# PCB-BI16-3x5_1.net
KiCad netlist of a schematic drawn in EAGLE
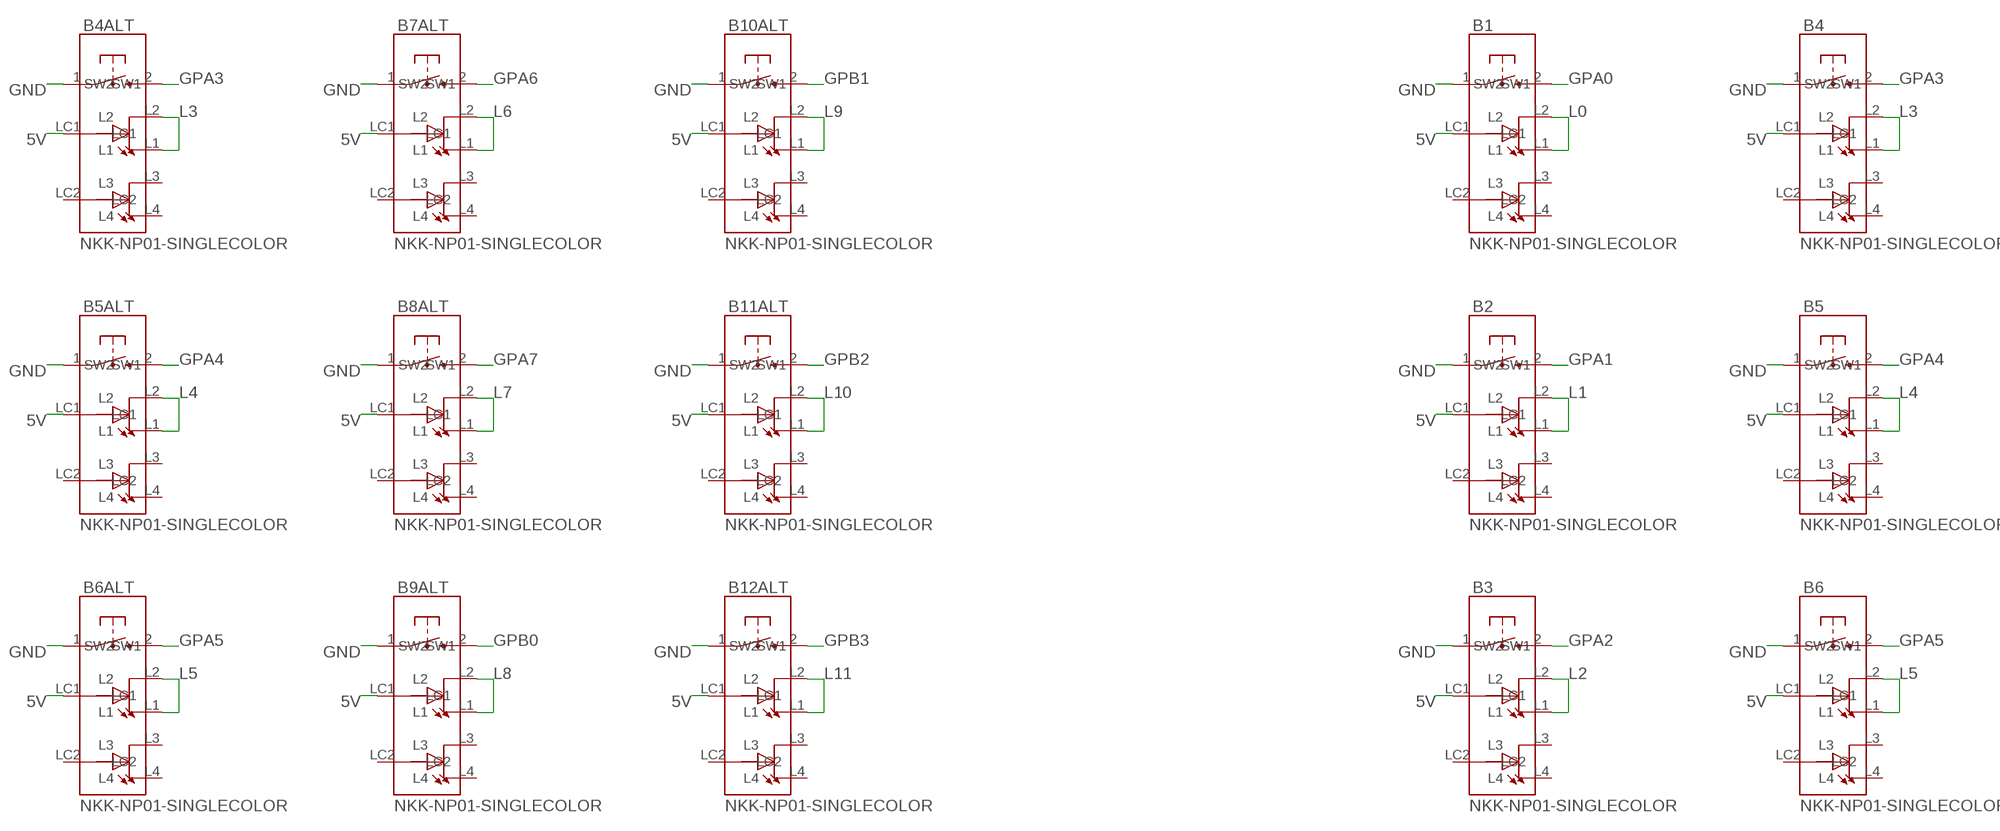
[diagram p0: schematic, sheet 1, part 1 of 2]
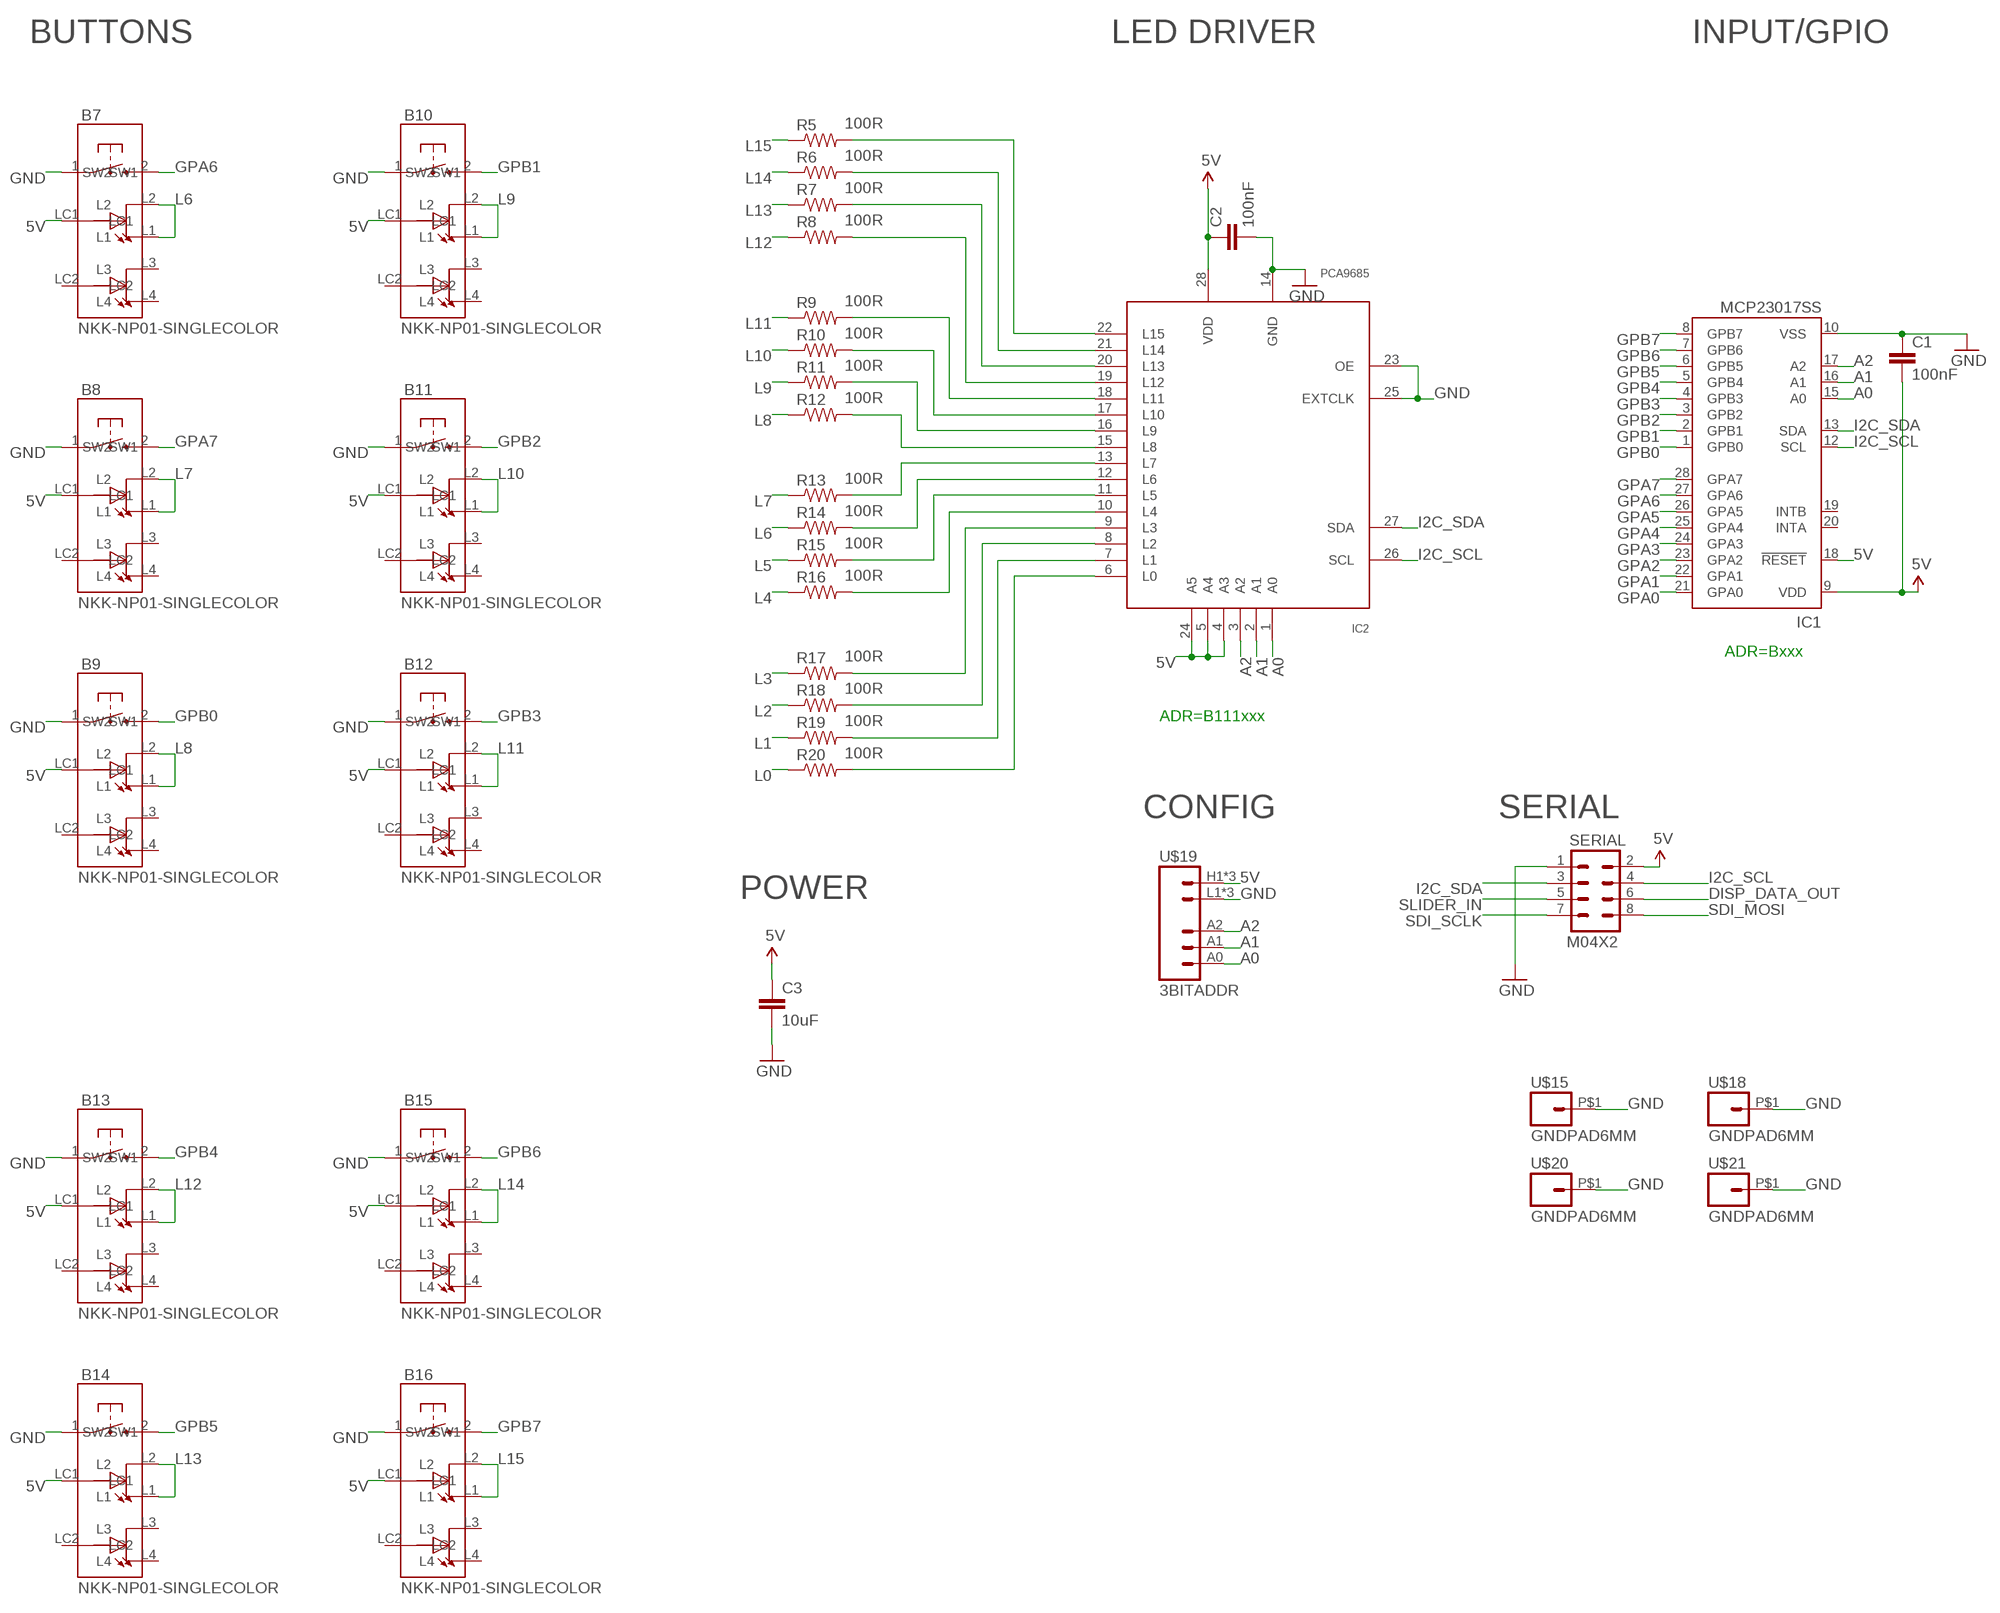
[diagram p1: schematic, sheet 1, part 2 of 2]

(export (version "E")
  (design (tool "Eeschema 10.0.6"))
  (components
    (comp (ref "B1")
      (value "NKK-NP01-SINGLECOLOR")
      (footprint "eagle-import:NKK-NP01")
      (libsource (lib "eagle-import") (part "NKK-NP01-SINGLECOLOR"))
    )
    (comp (ref "B2")
      (value "NKK-NP01-SINGLECOLOR")
      (footprint "eagle-import:NKK-NP01")
      (libsource (lib "eagle-import") (part "NKK-NP01-SINGLECOLOR"))
    )
    (comp (ref "B3")
      (value "NKK-NP01-SINGLECOLOR")
      (footprint "eagle-import:NKK-NP01")
      (libsource (lib "eagle-import") (part "NKK-NP01-SINGLECOLOR"))
    )
    (comp (ref "B4")
      (value "NKK-NP01-SINGLECOLOR")
      (footprint "eagle-import:NKK-NP01")
      (libsource (lib "eagle-import") (part "NKK-NP01-SINGLECOLOR"))
    )
    (comp (ref "B4ALT")
      (value "NKK-NP01-SINGLECOLOR")
      (footprint "eagle-import:NKK-NP01")
      (libsource (lib "eagle-import") (part "NKK-NP01-SINGLECOLOR"))
    )
    (comp (ref "B5")
      (value "NKK-NP01-SINGLECOLOR")
      (footprint "eagle-import:NKK-NP01")
      (libsource (lib "eagle-import") (part "NKK-NP01-SINGLECOLOR"))
    )
    (comp (ref "B5ALT")
      (value "NKK-NP01-SINGLECOLOR")
      (footprint "eagle-import:NKK-NP01")
      (libsource (lib "eagle-import") (part "NKK-NP01-SINGLECOLOR"))
    )
    (comp (ref "B6")
      (value "NKK-NP01-SINGLECOLOR")
      (footprint "eagle-import:NKK-NP01")
      (libsource (lib "eagle-import") (part "NKK-NP01-SINGLECOLOR"))
    )
    (comp (ref "B6ALT")
      (value "NKK-NP01-SINGLECOLOR")
      (footprint "eagle-import:NKK-NP01")
      (libsource (lib "eagle-import") (part "NKK-NP01-SINGLECOLOR"))
    )
    (comp (ref "B7")
      (value "NKK-NP01-SINGLECOLOR")
      (footprint "eagle-import:NKK-NP01")
      (libsource (lib "eagle-import") (part "NKK-NP01-SINGLECOLOR"))
    )
    (comp (ref "B7ALT")
      (value "NKK-NP01-SINGLECOLOR")
      (footprint "eagle-import:NKK-NP01")
      (libsource (lib "eagle-import") (part "NKK-NP01-SINGLECOLOR"))
    )
    (comp (ref "B8")
      (value "NKK-NP01-SINGLECOLOR")
      (footprint "eagle-import:NKK-NP01")
      (libsource (lib "eagle-import") (part "NKK-NP01-SINGLECOLOR"))
    )
    (comp (ref "B8ALT")
      (value "NKK-NP01-SINGLECOLOR")
      (footprint "eagle-import:NKK-NP01")
      (libsource (lib "eagle-import") (part "NKK-NP01-SINGLECOLOR"))
    )
    (comp (ref "B9")
      (value "NKK-NP01-SINGLECOLOR")
      (footprint "eagle-import:NKK-NP01")
      (libsource (lib "eagle-import") (part "NKK-NP01-SINGLECOLOR"))
    )
    (comp (ref "B9ALT")
      (value "NKK-NP01-SINGLECOLOR")
      (footprint "eagle-import:NKK-NP01")
      (libsource (lib "eagle-import") (part "NKK-NP01-SINGLECOLOR"))
    )
    (comp (ref "B10")
      (value "NKK-NP01-SINGLECOLOR")
      (footprint "eagle-import:NKK-NP01")
      (libsource (lib "eagle-import") (part "NKK-NP01-SINGLECOLOR"))
    )
    (comp (ref "B10ALT")
      (value "NKK-NP01-SINGLECOLOR")
      (footprint "eagle-import:NKK-NP01")
      (libsource (lib "eagle-import") (part "NKK-NP01-SINGLECOLOR"))
    )
    (comp (ref "B11")
      (value "NKK-NP01-SINGLECOLOR")
      (footprint "eagle-import:NKK-NP01")
      (libsource (lib "eagle-import") (part "NKK-NP01-SINGLECOLOR"))
    )
    (comp (ref "B11ALT")
      (value "NKK-NP01-SINGLECOLOR")
      (footprint "eagle-import:NKK-NP01")
      (libsource (lib "eagle-import") (part "NKK-NP01-SINGLECOLOR"))
    )
    (comp (ref "B12")
      (value "NKK-NP01-SINGLECOLOR")
      (footprint "eagle-import:NKK-NP01")
      (libsource (lib "eagle-import") (part "NKK-NP01-SINGLECOLOR"))
    )
    (comp (ref "B12ALT")
      (value "NKK-NP01-SINGLECOLOR")
      (footprint "eagle-import:NKK-NP01")
      (libsource (lib "eagle-import") (part "NKK-NP01-SINGLECOLOR"))
    )
    (comp (ref "B13")
      (value "NKK-NP01-SINGLECOLOR")
      (footprint "eagle-import:NKK-NP01")
      (libsource (lib "eagle-import") (part "NKK-NP01-SINGLECOLOR"))
    )
    (comp (ref "B14")
      (value "NKK-NP01-SINGLECOLOR")
      (footprint "eagle-import:NKK-NP01")
      (libsource (lib "eagle-import") (part "NKK-NP01-SINGLECOLOR"))
    )
    (comp (ref "B15")
      (value "NKK-NP01-SINGLECOLOR")
      (footprint "eagle-import:NKK-NP01")
      (libsource (lib "eagle-import") (part "NKK-NP01-SINGLECOLOR"))
    )
    (comp (ref "B16")
      (value "NKK-NP01-SINGLECOLOR")
      (footprint "eagle-import:NKK-NP01")
      (libsource (lib "eagle-import") (part "NKK-NP01-SINGLECOLOR"))
    )
    (comp (ref "C1")
      (value "100nF")
      (footprint "eagle-import:0603-CAP")
      (libsource (lib "eagle-import") (part "CAP0603-CAP"))
    )
    (comp (ref "C2")
      (value "100nF")
      (footprint "eagle-import:0603-CAP")
      (libsource (lib "eagle-import") (part "CAP0603-CAP"))
    )
    (comp (ref "C3")
      (value "10uF")
      (footprint "eagle-import:0805")
      (libsource (lib "eagle-import") (part "CAP0805"))
    )
    (comp (ref "IC1")
      (value "MCP23017SS")
      (footprint "eagle-import:SSOP28")
      (fields
        (field (name "MF") "MICROCHIP")
        (field (name "MPN") "MCP23017-E/SS")
        (field (name "MPN_1") "MCP23017-E/SS")
        (field (name "OC_FARNELL") "1467674")
        (field (name "OC_NEWARK") "31K2960")
      )
      (libsource (lib "eagle-import") (part "MCP23017SS"))
    )
    (comp (ref "IC2")
      (value "PCA9685")
      (footprint "eagle-import:TSSOP28")
      (libsource (lib "eagle-import") (part "PCA9685"))
    )
    (comp (ref "R5")
      (value "100R")
      (footprint "eagle-import:0603-RES")
      (libsource (lib "eagle-import") (part "RESISTOR0603-RES"))
    )
    (comp (ref "R6")
      (value "100R")
      (footprint "eagle-import:0603-RES")
      (libsource (lib "eagle-import") (part "RESISTOR0603-RES"))
    )
    (comp (ref "R7")
      (value "100R")
      (footprint "eagle-import:0603-RES")
      (libsource (lib "eagle-import") (part "RESISTOR0603-RES"))
    )
    (comp (ref "R8")
      (value "100R")
      (footprint "eagle-import:0603-RES")
      (libsource (lib "eagle-import") (part "RESISTOR0603-RES"))
    )
    (comp (ref "R9")
      (value "100R")
      (footprint "eagle-import:0603-RES")
      (libsource (lib "eagle-import") (part "RESISTOR0603-RES"))
    )
    (comp (ref "R10")
      (value "100R")
      (footprint "eagle-import:0603-RES")
      (libsource (lib "eagle-import") (part "RESISTOR0603-RES"))
    )
    (comp (ref "R11")
      (value "100R")
      (footprint "eagle-import:0603-RES")
      (libsource (lib "eagle-import") (part "RESISTOR0603-RES"))
    )
    (comp (ref "R12")
      (value "100R")
      (footprint "eagle-import:0603-RES")
      (libsource (lib "eagle-import") (part "RESISTOR0603-RES"))
    )
    (comp (ref "R13")
      (value "100R")
      (footprint "eagle-import:0603-RES")
      (libsource (lib "eagle-import") (part "RESISTOR0603-RES"))
    )
    (comp (ref "R14")
      (value "100R")
      (footprint "eagle-import:0603-RES")
      (libsource (lib "eagle-import") (part "RESISTOR0603-RES"))
    )
    (comp (ref "R15")
      (value "100R")
      (footprint "eagle-import:0603-RES")
      (libsource (lib "eagle-import") (part "RESISTOR0603-RES"))
    )
    (comp (ref "R16")
      (value "100R")
      (footprint "eagle-import:0603-RES")
      (libsource (lib "eagle-import") (part "RESISTOR0603-RES"))
    )
    (comp (ref "R17")
      (value "100R")
      (footprint "eagle-import:0603-RES")
      (libsource (lib "eagle-import") (part "RESISTOR0603-RES"))
    )
    (comp (ref "R18")
      (value "100R")
      (footprint "eagle-import:0603-RES")
      (libsource (lib "eagle-import") (part "RESISTOR0603-RES"))
    )
    (comp (ref "R19")
      (value "100R")
      (footprint "eagle-import:0603-RES")
      (libsource (lib "eagle-import") (part "RESISTOR0603-RES"))
    )
    (comp (ref "R20")
      (value "100R")
      (footprint "eagle-import:0603-RES")
      (libsource (lib "eagle-import") (part "RESISTOR0603-RES"))
    )
    (comp (ref "SERIAL")
      (value "M04X2")
      (footprint "eagle-import:2X4")
      (libsource (lib "eagle-import") (part "M04X2"))
    )
    (comp (ref "U$15")
      (value "GNDPAD6MM")
      (footprint "eagle-import:3.2MMPAD6MM")
      (libsource (lib "eagle-import") (part "GNDPAD6MM"))
    )
    (comp (ref "U$18")
      (value "GNDPAD6MM")
      (footprint "eagle-import:3.2MMPAD6MM")
      (libsource (lib "eagle-import") (part "GNDPAD6MM"))
    )
    (comp (ref "U$19")
      (value "3BITADDR")
      (footprint "eagle-import:3BITADDR")
      (libsource (lib "eagle-import") (part "3BITADDR"))
    )
    (comp (ref "U$20")
      (value "GNDPAD6MM")
      (footprint "eagle-import:3.2MMPAD6MM")
      (libsource (lib "eagle-import") (part "GNDPAD6MM"))
    )
    (comp (ref "U$21")
      (value "GNDPAD6MM")
      (footprint "eagle-import:3.2MMPAD6MM")
      (libsource (lib "eagle-import") (part "GNDPAD6MM"))
    )
  )
  (nets
    (net (code "1") (name "5V") (class "Default")
      (node (ref "B1") (pin "LC1") (pinfunction "LC1_LC1") (pintype "bidirectional"))
      (node (ref "B10") (pin "LC1") (pinfunction "LC1_LC1") (pintype "bidirectional"))
      (node (ref "B10ALT") (pin "LC1") (pinfunction "LC1_LC1") (pintype "bidirectional"))
      (node (ref "B11") (pin "LC1") (pinfunction "LC1_LC1") (pintype "bidirectional"))
      (node (ref "B11ALT") (pin "LC1") (pinfunction "LC1_LC1") (pintype "bidirectional"))
      (node (ref "B12") (pin "LC1") (pinfunction "LC1_LC1") (pintype "bidirectional"))
      (node (ref "B12ALT") (pin "LC1") (pinfunction "LC1_LC1") (pintype "bidirectional"))
      (node (ref "B13") (pin "LC1") (pinfunction "LC1_LC1") (pintype "bidirectional"))
      (node (ref "B14") (pin "LC1") (pinfunction "LC1_LC1") (pintype "bidirectional"))
      (node (ref "B15") (pin "LC1") (pinfunction "LC1_LC1") (pintype "bidirectional"))
      (node (ref "B16") (pin "LC1") (pinfunction "LC1_LC1") (pintype "bidirectional"))
      (node (ref "B2") (pin "LC1") (pinfunction "LC1_LC1") (pintype "bidirectional"))
      (node (ref "B3") (pin "LC1") (pinfunction "LC1_LC1") (pintype "bidirectional"))
      (node (ref "B4") (pin "LC1") (pinfunction "LC1_LC1") (pintype "bidirectional"))
      (node (ref "B4ALT") (pin "LC1") (pinfunction "LC1_LC1") (pintype "bidirectional"))
      (node (ref "B5") (pin "LC1") (pinfunction "LC1_LC1") (pintype "bidirectional"))
      (node (ref "B5ALT") (pin "LC1") (pinfunction "LC1_LC1") (pintype "bidirectional"))
      (node (ref "B6") (pin "LC1") (pinfunction "LC1_LC1") (pintype "bidirectional"))
      (node (ref "B6ALT") (pin "LC1") (pinfunction "LC1_LC1") (pintype "bidirectional"))
      (node (ref "B7") (pin "LC1") (pinfunction "LC1_LC1") (pintype "bidirectional"))
      (node (ref "B7ALT") (pin "LC1") (pinfunction "LC1_LC1") (pintype "bidirectional"))
      (node (ref "B8") (pin "LC1") (pinfunction "LC1_LC1") (pintype "bidirectional"))
      (node (ref "B8ALT") (pin "LC1") (pinfunction "LC1_LC1") (pintype "bidirectional"))
      (node (ref "B9") (pin "LC1") (pinfunction "LC1_LC1") (pintype "bidirectional"))
      (node (ref "B9ALT") (pin "LC1") (pinfunction "LC1_LC1") (pintype "bidirectional"))
      (node (ref "C1") (pin "2") (pinfunction "2_2") (pintype "passive"))
      (node (ref "C2") (pin "1") (pinfunction "1_1") (pintype "passive"))
      (node (ref "C3") (pin "1") (pinfunction "1_1") (pintype "passive"))
      (node (ref "IC1") (pin "18") (pinfunction "~{RESET}_18") (pintype "input"))
      (node (ref "IC1") (pin "9") (pinfunction "VDD_9") (pintype "power_in"))
      (node (ref "IC2") (pin "24") (pinfunction "A5_24") (pintype "input"))
      (node (ref "IC2") (pin "28") (pinfunction "VDD_28") (pintype "power_in"))
      (node (ref "IC2") (pin "4") (pinfunction "A3_4") (pintype "input"))
      (node (ref "IC2") (pin "5") (pinfunction "A4_5") (pintype "input"))
      (node (ref "SERIAL") (pin "2") (pinfunction "2_2") (pintype "passive"))
      (node (ref "U$19") (pin "H1") (pinfunction "VCC_H1") (pintype "passive"))
      (node (ref "U$19") (pin "H2") (pinfunction "VCC_H2") (pintype "passive"))
      (node (ref "U$19") (pin "H3") (pinfunction "VCC_H3") (pintype "passive"))
    )
    (net (code "2") (name "A0") (class "Default")
      (node (ref "IC1") (pin "15") (pinfunction "A0_15") (pintype "input"))
      (node (ref "IC2") (pin "1") (pinfunction "A0_1") (pintype "input"))
      (node (ref "U$19") (pin "A0") (pinfunction "A0_A0") (pintype "passive"))
    )
    (net (code "3") (name "A1") (class "Default")
      (node (ref "IC1") (pin "16") (pinfunction "A1_16") (pintype "input"))
      (node (ref "IC2") (pin "2") (pinfunction "A1_2") (pintype "input"))
      (node (ref "U$19") (pin "A1") (pinfunction "A1_A1") (pintype "passive"))
    )
    (net (code "4") (name "A2") (class "Default")
      (node (ref "IC1") (pin "17") (pinfunction "A2_17") (pintype "input"))
      (node (ref "IC2") (pin "3") (pinfunction "A2_3") (pintype "input"))
      (node (ref "U$19") (pin "A2") (pinfunction "A2_A2") (pintype "passive"))
    )
    (net (code "5") (name "DISP_DATA_OUT") (class "Default")
      (node (ref "SERIAL") (pin "6") (pinfunction "6_6") (pintype "passive"))
    )
    (net (code "6") (name "GND") (class "Default")
      (node (ref "B1") (pin "1") (pinfunction "SW1_1") (pintype "bidirectional"))
      (node (ref "B10") (pin "1") (pinfunction "SW1_1") (pintype "bidirectional"))
      (node (ref "B10ALT") (pin "1") (pinfunction "SW1_1") (pintype "bidirectional"))
      (node (ref "B11") (pin "1") (pinfunction "SW1_1") (pintype "bidirectional"))
      (node (ref "B11ALT") (pin "1") (pinfunction "SW1_1") (pintype "bidirectional"))
      (node (ref "B12") (pin "1") (pinfunction "SW1_1") (pintype "bidirectional"))
      (node (ref "B12ALT") (pin "1") (pinfunction "SW1_1") (pintype "bidirectional"))
      (node (ref "B13") (pin "1") (pinfunction "SW1_1") (pintype "bidirectional"))
      (node (ref "B14") (pin "1") (pinfunction "SW1_1") (pintype "bidirectional"))
      (node (ref "B15") (pin "1") (pinfunction "SW1_1") (pintype "bidirectional"))
      (node (ref "B16") (pin "1") (pinfunction "SW1_1") (pintype "bidirectional"))
      (node (ref "B2") (pin "1") (pinfunction "SW1_1") (pintype "bidirectional"))
      (node (ref "B3") (pin "1") (pinfunction "SW1_1") (pintype "bidirectional"))
      (node (ref "B4") (pin "1") (pinfunction "SW1_1") (pintype "bidirectional"))
      (node (ref "B4ALT") (pin "1") (pinfunction "SW1_1") (pintype "bidirectional"))
      (node (ref "B5") (pin "1") (pinfunction "SW1_1") (pintype "bidirectional"))
      (node (ref "B5ALT") (pin "1") (pinfunction "SW1_1") (pintype "bidirectional"))
      (node (ref "B6") (pin "1") (pinfunction "SW1_1") (pintype "bidirectional"))
      (node (ref "B6ALT") (pin "1") (pinfunction "SW1_1") (pintype "bidirectional"))
      (node (ref "B7") (pin "1") (pinfunction "SW1_1") (pintype "bidirectional"))
      (node (ref "B7ALT") (pin "1") (pinfunction "SW1_1") (pintype "bidirectional"))
      (node (ref "B8") (pin "1") (pinfunction "SW1_1") (pintype "bidirectional"))
      (node (ref "B8ALT") (pin "1") (pinfunction "SW1_1") (pintype "bidirectional"))
      (node (ref "B9") (pin "1") (pinfunction "SW1_1") (pintype "bidirectional"))
      (node (ref "B9ALT") (pin "1") (pinfunction "SW1_1") (pintype "bidirectional"))
      (node (ref "C1") (pin "1") (pinfunction "1_1") (pintype "passive"))
      (node (ref "C2") (pin "2") (pinfunction "2_2") (pintype "passive"))
      (node (ref "C3") (pin "2") (pinfunction "2_2") (pintype "passive"))
      (node (ref "IC1") (pin "10") (pinfunction "VSS_10") (pintype "power_in"))
      (node (ref "IC2") (pin "14") (pinfunction "GND_14") (pintype "power_in"))
      (node (ref "IC2") (pin "23") (pinfunction "OE_23") (pintype "input"))
      (node (ref "IC2") (pin "25") (pinfunction "EXTCLK_25") (pintype "input"))
      (node (ref "SERIAL") (pin "1") (pinfunction "1_1") (pintype "passive"))
      (node (ref "U$15") (pin "P$1") (pinfunction "1_P$1") (pintype "passive"))
      (node (ref "U$18") (pin "P$1") (pinfunction "1_P$1") (pintype "passive"))
      (node (ref "U$19") (pin "L1") (pinfunction "GND_L1") (pintype "passive"))
      (node (ref "U$19") (pin "L2") (pinfunction "GND_L2") (pintype "passive"))
      (node (ref "U$19") (pin "L3") (pinfunction "GND_L3") (pintype "passive"))
      (node (ref "U$20") (pin "P$1") (pinfunction "1_P$1") (pintype "passive"))
      (node (ref "U$21") (pin "P$1") (pinfunction "1_P$1") (pintype "passive"))
    )
    (net (code "7") (name "GPA0") (class "Default")
      (node (ref "B1") (pin "2") (pinfunction "SW2_2") (pintype "bidirectional"))
      (node (ref "IC1") (pin "21") (pinfunction "GPA0_21") (pintype "bidirectional"))
    )
    (net (code "8") (name "GPA1") (class "Default")
      (node (ref "B2") (pin "2") (pinfunction "SW2_2") (pintype "bidirectional"))
      (node (ref "IC1") (pin "22") (pinfunction "GPA1_22") (pintype "bidirectional"))
    )
    (net (code "9") (name "GPA2") (class "Default")
      (node (ref "B3") (pin "2") (pinfunction "SW2_2") (pintype "bidirectional"))
      (node (ref "IC1") (pin "23") (pinfunction "GPA2_23") (pintype "bidirectional"))
    )
    (net (code "10") (name "GPA3") (class "Default")
      (node (ref "B4") (pin "2") (pinfunction "SW2_2") (pintype "bidirectional"))
      (node (ref "B4ALT") (pin "2") (pinfunction "SW2_2") (pintype "bidirectional"))
      (node (ref "IC1") (pin "24") (pinfunction "GPA3_24") (pintype "bidirectional"))
    )
    (net (code "11") (name "GPA4") (class "Default")
      (node (ref "B5") (pin "2") (pinfunction "SW2_2") (pintype "bidirectional"))
      (node (ref "B5ALT") (pin "2") (pinfunction "SW2_2") (pintype "bidirectional"))
      (node (ref "IC1") (pin "25") (pinfunction "GPA4_25") (pintype "bidirectional"))
    )
    (net (code "12") (name "GPA5") (class "Default")
      (node (ref "B6") (pin "2") (pinfunction "SW2_2") (pintype "bidirectional"))
      (node (ref "B6ALT") (pin "2") (pinfunction "SW2_2") (pintype "bidirectional"))
      (node (ref "IC1") (pin "26") (pinfunction "GPA5_26") (pintype "bidirectional"))
    )
    (net (code "13") (name "GPA6") (class "Default")
      (node (ref "B7") (pin "2") (pinfunction "SW2_2") (pintype "bidirectional"))
      (node (ref "B7ALT") (pin "2") (pinfunction "SW2_2") (pintype "bidirectional"))
      (node (ref "IC1") (pin "27") (pinfunction "GPA6_27") (pintype "bidirectional"))
    )
    (net (code "14") (name "GPA7") (class "Default")
      (node (ref "B8") (pin "2") (pinfunction "SW2_2") (pintype "bidirectional"))
      (node (ref "B8ALT") (pin "2") (pinfunction "SW2_2") (pintype "bidirectional"))
      (node (ref "IC1") (pin "28") (pinfunction "GPA7_28") (pintype "bidirectional"))
    )
    (net (code "15") (name "GPB0") (class "Default")
      (node (ref "B9") (pin "2") (pinfunction "SW2_2") (pintype "bidirectional"))
      (node (ref "B9ALT") (pin "2") (pinfunction "SW2_2") (pintype "bidirectional"))
      (node (ref "IC1") (pin "1") (pinfunction "GPB0_1") (pintype "bidirectional"))
    )
    (net (code "16") (name "GPB1") (class "Default")
      (node (ref "B10") (pin "2") (pinfunction "SW2_2") (pintype "bidirectional"))
      (node (ref "B10ALT") (pin "2") (pinfunction "SW2_2") (pintype "bidirectional"))
      (node (ref "IC1") (pin "2") (pinfunction "GPB1_2") (pintype "bidirectional"))
    )
    (net (code "17") (name "GPB2") (class "Default")
      (node (ref "B11") (pin "2") (pinfunction "SW2_2") (pintype "bidirectional"))
      (node (ref "B11ALT") (pin "2") (pinfunction "SW2_2") (pintype "bidirectional"))
      (node (ref "IC1") (pin "3") (pinfunction "GPB2_3") (pintype "bidirectional"))
    )
    (net (code "18") (name "GPB3") (class "Default")
      (node (ref "B12") (pin "2") (pinfunction "SW2_2") (pintype "bidirectional"))
      (node (ref "B12ALT") (pin "2") (pinfunction "SW2_2") (pintype "bidirectional"))
      (node (ref "IC1") (pin "4") (pinfunction "GPB3_4") (pintype "bidirectional"))
    )
    (net (code "19") (name "GPB4") (class "Default")
      (node (ref "B13") (pin "2") (pinfunction "SW2_2") (pintype "bidirectional"))
      (node (ref "IC1") (pin "5") (pinfunction "GPB4_5") (pintype "bidirectional"))
    )
    (net (code "20") (name "GPB5") (class "Default")
      (node (ref "B14") (pin "2") (pinfunction "SW2_2") (pintype "bidirectional"))
      (node (ref "IC1") (pin "6") (pinfunction "GPB5_6") (pintype "bidirectional"))
    )
    (net (code "21") (name "GPB6") (class "Default")
      (node (ref "B15") (pin "2") (pinfunction "SW2_2") (pintype "bidirectional"))
      (node (ref "IC1") (pin "7") (pinfunction "GPB6_7") (pintype "bidirectional"))
    )
    (net (code "22") (name "GPB7") (class "Default")
      (node (ref "B16") (pin "2") (pinfunction "SW2_2") (pintype "bidirectional"))
      (node (ref "IC1") (pin "8") (pinfunction "GPB7_8") (pintype "bidirectional"))
    )
    (net (code "23") (name "I2C_SCL") (class "Default")
      (node (ref "IC1") (pin "12") (pinfunction "SCL_12") (pintype "input"))
      (node (ref "IC2") (pin "26") (pinfunction "SCL_26") (pintype "input"))
      (node (ref "SERIAL") (pin "4") (pinfunction "4_4") (pintype "passive"))
    )
    (net (code "24") (name "I2C_SDA") (class "Default")
      (node (ref "IC1") (pin "13") (pinfunction "SDA_13") (pintype "bidirectional"))
      (node (ref "IC2") (pin "27") (pinfunction "SDA_27") (pintype "input"))
      (node (ref "SERIAL") (pin "3") (pinfunction "3_3") (pintype "passive"))
    )
    (net (code "25") (name "L0") (class "Default")
      (node (ref "B1") (pin "L1") (pinfunction "L1_L1") (pintype "bidirectional"))
      (node (ref "B1") (pin "L2") (pinfunction "L2_L2") (pintype "bidirectional"))
      (node (ref "R20") (pin "1") (pinfunction "1_1") (pintype "passive"))
    )
    (net (code "26") (name "L1") (class "Default")
      (node (ref "B2") (pin "L1") (pinfunction "L1_L1") (pintype "bidirectional"))
      (node (ref "B2") (pin "L2") (pinfunction "L2_L2") (pintype "bidirectional"))
      (node (ref "R19") (pin "1") (pinfunction "1_1") (pintype "passive"))
    )
    (net (code "27") (name "L2") (class "Default")
      (node (ref "B3") (pin "L1") (pinfunction "L1_L1") (pintype "bidirectional"))
      (node (ref "B3") (pin "L2") (pinfunction "L2_L2") (pintype "bidirectional"))
      (node (ref "R18") (pin "1") (pinfunction "1_1") (pintype "passive"))
    )
    (net (code "28") (name "L3") (class "Default")
      (node (ref "B4") (pin "L1") (pinfunction "L1_L1") (pintype "bidirectional"))
      (node (ref "B4") (pin "L2") (pinfunction "L2_L2") (pintype "bidirectional"))
      (node (ref "B4ALT") (pin "L1") (pinfunction "L1_L1") (pintype "bidirectional"))
      (node (ref "B4ALT") (pin "L2") (pinfunction "L2_L2") (pintype "bidirectional"))
      (node (ref "R17") (pin "1") (pinfunction "1_1") (pintype "passive"))
    )
    (net (code "29") (name "L4") (class "Default")
      (node (ref "B5") (pin "L1") (pinfunction "L1_L1") (pintype "bidirectional"))
      (node (ref "B5") (pin "L2") (pinfunction "L2_L2") (pintype "bidirectional"))
      (node (ref "B5ALT") (pin "L1") (pinfunction "L1_L1") (pintype "bidirectional"))
      (node (ref "B5ALT") (pin "L2") (pinfunction "L2_L2") (pintype "bidirectional"))
      (node (ref "R16") (pin "1") (pinfunction "1_1") (pintype "passive"))
    )
    (net (code "30") (name "L5") (class "Default")
      (node (ref "B6") (pin "L1") (pinfunction "L1_L1") (pintype "bidirectional"))
      (node (ref "B6") (pin "L2") (pinfunction "L2_L2") (pintype "bidirectional"))
      (node (ref "B6ALT") (pin "L1") (pinfunction "L1_L1") (pintype "bidirectional"))
      (node (ref "B6ALT") (pin "L2") (pinfunction "L2_L2") (pintype "bidirectional"))
      (node (ref "R15") (pin "1") (pinfunction "1_1") (pintype "passive"))
    )
    (net (code "31") (name "L6") (class "Default")
      (node (ref "B7") (pin "L1") (pinfunction "L1_L1") (pintype "bidirectional"))
      (node (ref "B7") (pin "L2") (pinfunction "L2_L2") (pintype "bidirectional"))
      (node (ref "B7ALT") (pin "L1") (pinfunction "L1_L1") (pintype "bidirectional"))
      (node (ref "B7ALT") (pin "L2") (pinfunction "L2_L2") (pintype "bidirectional"))
      (node (ref "R14") (pin "1") (pinfunction "1_1") (pintype "passive"))
    )
    (net (code "32") (name "L7") (class "Default")
      (node (ref "B8") (pin "L1") (pinfunction "L1_L1") (pintype "bidirectional"))
      (node (ref "B8") (pin "L2") (pinfunction "L2_L2") (pintype "bidirectional"))
      (node (ref "B8ALT") (pin "L1") (pinfunction "L1_L1") (pintype "bidirectional"))
      (node (ref "B8ALT") (pin "L2") (pinfunction "L2_L2") (pintype "bidirectional"))
      (node (ref "R13") (pin "1") (pinfunction "1_1") (pintype "passive"))
    )
    (net (code "33") (name "L8") (class "Default")
      (node (ref "B9") (pin "L1") (pinfunction "L1_L1") (pintype "bidirectional"))
      (node (ref "B9") (pin "L2") (pinfunction "L2_L2") (pintype "bidirectional"))
      (node (ref "B9ALT") (pin "L1") (pinfunction "L1_L1") (pintype "bidirectional"))
      (node (ref "B9ALT") (pin "L2") (pinfunction "L2_L2") (pintype "bidirectional"))
      (node (ref "R12") (pin "1") (pinfunction "1_1") (pintype "passive"))
    )
    (net (code "34") (name "L9") (class "Default")
      (node (ref "B10") (pin "L1") (pinfunction "L1_L1") (pintype "bidirectional"))
      (node (ref "B10") (pin "L2") (pinfunction "L2_L2") (pintype "bidirectional"))
      (node (ref "B10ALT") (pin "L1") (pinfunction "L1_L1") (pintype "bidirectional"))
      (node (ref "B10ALT") (pin "L2") (pinfunction "L2_L2") (pintype "bidirectional"))
      (node (ref "R11") (pin "1") (pinfunction "1_1") (pintype "passive"))
    )
    (net (code "35") (name "L10") (class "Default")
      (node (ref "B11") (pin "L1") (pinfunction "L1_L1") (pintype "bidirectional"))
      (node (ref "B11") (pin "L2") (pinfunction "L2_L2") (pintype "bidirectional"))
      (node (ref "B11ALT") (pin "L1") (pinfunction "L1_L1") (pintype "bidirectional"))
      (node (ref "B11ALT") (pin "L2") (pinfunction "L2_L2") (pintype "bidirectional"))
      (node (ref "R10") (pin "1") (pinfunction "1_1") (pintype "passive"))
    )
    (net (code "36") (name "L11") (class "Default")
      (node (ref "B12") (pin "L1") (pinfunction "L1_L1") (pintype "bidirectional"))
      (node (ref "B12") (pin "L2") (pinfunction "L2_L2") (pintype "bidirectional"))
      (node (ref "B12ALT") (pin "L1") (pinfunction "L1_L1") (pintype "bidirectional"))
      (node (ref "B12ALT") (pin "L2") (pinfunction "L2_L2") (pintype "bidirectional"))
      (node (ref "R9") (pin "1") (pinfunction "1_1") (pintype "passive"))
    )
    (net (code "37") (name "L12") (class "Default")
      (node (ref "B13") (pin "L1") (pinfunction "L1_L1") (pintype "bidirectional"))
      (node (ref "B13") (pin "L2") (pinfunction "L2_L2") (pintype "bidirectional"))
      (node (ref "R8") (pin "1") (pinfunction "1_1") (pintype "passive"))
    )
    (net (code "38") (name "L13") (class "Default")
      (node (ref "B14") (pin "L1") (pinfunction "L1_L1") (pintype "bidirectional"))
      (node (ref "B14") (pin "L2") (pinfunction "L2_L2") (pintype "bidirectional"))
      (node (ref "R7") (pin "1") (pinfunction "1_1") (pintype "passive"))
    )
    (net (code "39") (name "L14") (class "Default")
      (node (ref "B15") (pin "L1") (pinfunction "L1_L1") (pintype "bidirectional"))
      (node (ref "B15") (pin "L2") (pinfunction "L2_L2") (pintype "bidirectional"))
      (node (ref "R6") (pin "1") (pinfunction "1_1") (pintype "passive"))
    )
    (net (code "40") (name "L15") (class "Default")
      (node (ref "B16") (pin "L1") (pinfunction "L1_L1") (pintype "bidirectional"))
      (node (ref "B16") (pin "L2") (pinfunction "L2_L2") (pintype "bidirectional"))
      (node (ref "R5") (pin "1") (pinfunction "1_1") (pintype "passive"))
    )
    (net (code "41") (name "Net-(IC2-L0)") (class "Default")
      (node (ref "IC2") (pin "6") (pinfunction "L0_6") (pintype "output"))
      (node (ref "R20") (pin "2") (pinfunction "2_2") (pintype "passive"))
    )
    (net (code "42") (name "Net-(IC2-L1)") (class "Default")
      (node (ref "IC2") (pin "7") (pinfunction "L1_7") (pintype "output"))
      (node (ref "R19") (pin "2") (pinfunction "2_2") (pintype "passive"))
    )
    (net (code "43") (name "Net-(IC2-L2)") (class "Default")
      (node (ref "IC2") (pin "8") (pinfunction "L2_8") (pintype "output"))
      (node (ref "R18") (pin "2") (pinfunction "2_2") (pintype "passive"))
    )
    (net (code "44") (name "Net-(IC2-L3)") (class "Default")
      (node (ref "IC2") (pin "9") (pinfunction "L3_9") (pintype "output"))
      (node (ref "R17") (pin "2") (pinfunction "2_2") (pintype "passive"))
    )
    (net (code "45") (name "Net-(IC2-L4)") (class "Default")
      (node (ref "IC2") (pin "10") (pinfunction "L4_10") (pintype "output"))
      (node (ref "R16") (pin "2") (pinfunction "2_2") (pintype "passive"))
    )
    (net (code "46") (name "Net-(IC2-L5)") (class "Default")
      (node (ref "IC2") (pin "11") (pinfunction "L5_11") (pintype "output"))
      (node (ref "R15") (pin "2") (pinfunction "2_2") (pintype "passive"))
    )
    (net (code "47") (name "Net-(IC2-L6)") (class "Default")
      (node (ref "IC2") (pin "12") (pinfunction "L6_12") (pintype "output"))
      (node (ref "R14") (pin "2") (pinfunction "2_2") (pintype "passive"))
    )
    (net (code "48") (name "Net-(IC2-L7)") (class "Default")
      (node (ref "IC2") (pin "13") (pinfunction "L7_13") (pintype "output"))
      (node (ref "R13") (pin "2") (pinfunction "2_2") (pintype "passive"))
    )
    (net (code "49") (name "Net-(IC2-L8)") (class "Default")
      (node (ref "IC2") (pin "15") (pinfunction "L8_15") (pintype "output"))
      (node (ref "R12") (pin "2") (pinfunction "2_2") (pintype "passive"))
    )
    (net (code "50") (name "Net-(IC2-L9)") (class "Default")
      (node (ref "IC2") (pin "16") (pinfunction "L9_16") (pintype "output"))
      (node (ref "R11") (pin "2") (pinfunction "2_2") (pintype "passive"))
    )
    (net (code "51") (name "Net-(IC2-L10)") (class "Default")
      (node (ref "IC2") (pin "17") (pinfunction "L10_17") (pintype "output"))
      (node (ref "R10") (pin "2") (pinfunction "2_2") (pintype "passive"))
    )
    (net (code "52") (name "Net-(IC2-L11)") (class "Default")
      (node (ref "IC2") (pin "18") (pinfunction "L11_18") (pintype "output"))
      (node (ref "R9") (pin "2") (pinfunction "2_2") (pintype "passive"))
    )
    (net (code "53") (name "Net-(IC2-L12)") (class "Default")
      (node (ref "IC2") (pin "19") (pinfunction "L12_19") (pintype "output"))
      (node (ref "R8") (pin "2") (pinfunction "2_2") (pintype "passive"))
    )
    (net (code "54") (name "Net-(IC2-L13)") (class "Default")
      (node (ref "IC2") (pin "20") (pinfunction "L13_20") (pintype "output"))
      (node (ref "R7") (pin "2") (pinfunction "2_2") (pintype "passive"))
    )
    (net (code "55") (name "Net-(IC2-L14)") (class "Default")
      (node (ref "IC2") (pin "21") (pinfunction "L14_21") (pintype "output"))
      (node (ref "R6") (pin "2") (pinfunction "2_2") (pintype "passive"))
    )
    (net (code "56") (name "Net-(IC2-L15)") (class "Default")
      (node (ref "IC2") (pin "22") (pinfunction "L15_22") (pintype "output"))
      (node (ref "R5") (pin "2") (pinfunction "2_2") (pintype "passive"))
    )
    (net (code "57") (name "SDI_MOSI") (class "Default")
      (node (ref "SERIAL") (pin "8") (pinfunction "8_8") (pintype "passive"))
    )
    (net (code "58") (name "SDI_SCLK") (class "Default")
      (node (ref "SERIAL") (pin "7") (pinfunction "7_7") (pintype "passive"))
    )
    (net (code "59") (name "SLIDER_IN") (class "Default")
      (node (ref "SERIAL") (pin "5") (pinfunction "5_5") (pintype "passive"))
    )
    (net (code "60") (name "unconnected-(B1-PadL3)") (class "Default")
      (node (ref "B1") (pin "L3") (pinfunction "L3_L3") (pintype "bidirectional"))
    )
    (net (code "61") (name "unconnected-(B1-PadL4)") (class "Default")
      (node (ref "B1") (pin "L4") (pinfunction "L4_L4") (pintype "bidirectional"))
    )
    (net (code "62") (name "unconnected-(B1-PadLC2)") (class "Default")
      (node (ref "B1") (pin "LC2") (pinfunction "LC2_LC2") (pintype "bidirectional"))
    )
    (net (code "63") (name "unconnected-(B2-PadL3)") (class "Default")
      (node (ref "B2") (pin "L3") (pinfunction "L3_L3") (pintype "bidirectional"))
    )
    (net (code "64") (name "unconnected-(B2-PadL4)") (class "Default")
      (node (ref "B2") (pin "L4") (pinfunction "L4_L4") (pintype "bidirectional"))
    )
    (net (code "65") (name "unconnected-(B2-PadLC2)") (class "Default")
      (node (ref "B2") (pin "LC2") (pinfunction "LC2_LC2") (pintype "bidirectional"))
    )
    (net (code "66") (name "unconnected-(B3-PadL3)") (class "Default")
      (node (ref "B3") (pin "L3") (pinfunction "L3_L3") (pintype "bidirectional"))
    )
    (net (code "67") (name "unconnected-(B3-PadL4)") (class "Default")
      (node (ref "B3") (pin "L4") (pinfunction "L4_L4") (pintype "bidirectional"))
    )
    (net (code "68") (name "unconnected-(B3-PadLC2)") (class "Default")
      (node (ref "B3") (pin "LC2") (pinfunction "LC2_LC2") (pintype "bidirectional"))
    )
    (net (code "69") (name "unconnected-(B4-PadL3)") (class "Default")
      (node (ref "B4") (pin "L3") (pinfunction "L3_L3") (pintype "bidirectional"))
    )
    (net (code "70") (name "unconnected-(B4-PadL4)") (class "Default")
      (node (ref "B4") (pin "L4") (pinfunction "L4_L4") (pintype "bidirectional"))
    )
    (net (code "71") (name "unconnected-(B4-PadLC2)") (class "Default")
      (node (ref "B4") (pin "LC2") (pinfunction "LC2_LC2") (pintype "bidirectional"))
    )
    (net (code "72") (name "unconnected-(B4ALT-PadL3)") (class "Default")
      (node (ref "B4ALT") (pin "L3") (pinfunction "L3_L3") (pintype "bidirectional"))
    )
    (net (code "73") (name "unconnected-(B4ALT-PadL4)") (class "Default")
      (node (ref "B4ALT") (pin "L4") (pinfunction "L4_L4") (pintype "bidirectional"))
    )
    (net (code "74") (name "unconnected-(B4ALT-PadLC2)") (class "Default")
      (node (ref "B4ALT") (pin "LC2") (pinfunction "LC2_LC2") (pintype "bidirectional"))
    )
    (net (code "75") (name "unconnected-(B5-PadL3)") (class "Default")
      (node (ref "B5") (pin "L3") (pinfunction "L3_L3") (pintype "bidirectional"))
    )
    (net (code "76") (name "unconnected-(B5-PadL4)") (class "Default")
      (node (ref "B5") (pin "L4") (pinfunction "L4_L4") (pintype "bidirectional"))
    )
    (net (code "77") (name "unconnected-(B5-PadLC2)") (class "Default")
      (node (ref "B5") (pin "LC2") (pinfunction "LC2_LC2") (pintype "bidirectional"))
    )
    (net (code "78") (name "unconnected-(B5ALT-PadL3)") (class "Default")
      (node (ref "B5ALT") (pin "L3") (pinfunction "L3_L3") (pintype "bidirectional"))
    )
    (net (code "79") (name "unconnected-(B5ALT-PadL4)") (class "Default")
      (node (ref "B5ALT") (pin "L4") (pinfunction "L4_L4") (pintype "bidirectional"))
    )
    (net (code "80") (name "unconnected-(B5ALT-PadLC2)") (class "Default")
      (node (ref "B5ALT") (pin "LC2") (pinfunction "LC2_LC2") (pintype "bidirectional"))
    )
    (net (code "81") (name "unconnected-(B6-PadL3)") (class "Default")
      (node (ref "B6") (pin "L3") (pinfunction "L3_L3") (pintype "bidirectional"))
    )
    (net (code "82") (name "unconnected-(B6-PadL4)") (class "Default")
      (node (ref "B6") (pin "L4") (pinfunction "L4_L4") (pintype "bidirectional"))
    )
    (net (code "83") (name "unconnected-(B6-PadLC2)") (class "Default")
      (node (ref "B6") (pin "LC2") (pinfunction "LC2_LC2") (pintype "bidirectional"))
    )
    (net (code "84") (name "unconnected-(B6ALT-PadL3)") (class "Default")
      (node (ref "B6ALT") (pin "L3") (pinfunction "L3_L3") (pintype "bidirectional"))
    )
    (net (code "85") (name "unconnected-(B6ALT-PadL4)") (class "Default")
      (node (ref "B6ALT") (pin "L4") (pinfunction "L4_L4") (pintype "bidirectional"))
    )
    (net (code "86") (name "unconnected-(B6ALT-PadLC2)") (class "Default")
      (node (ref "B6ALT") (pin "LC2") (pinfunction "LC2_LC2") (pintype "bidirectional"))
    )
    (net (code "87") (name "unconnected-(B7-PadL3)") (class "Default")
      (node (ref "B7") (pin "L3") (pinfunction "L3_L3") (pintype "bidirectional"))
    )
    (net (code "88") (name "unconnected-(B7-PadL4)") (class "Default")
      (node (ref "B7") (pin "L4") (pinfunction "L4_L4") (pintype "bidirectional"))
    )
    (net (code "89") (name "unconnected-(B7-PadLC2)") (class "Default")
      (node (ref "B7") (pin "LC2") (pinfunction "LC2_LC2") (pintype "bidirectional"))
    )
    (net (code "90") (name "unconnected-(B7ALT-PadL3)") (class "Default")
      (node (ref "B7ALT") (pin "L3") (pinfunction "L3_L3") (pintype "bidirectional"))
    )
    (net (code "91") (name "unconnected-(B7ALT-PadL4)") (class "Default")
      (node (ref "B7ALT") (pin "L4") (pinfunction "L4_L4") (pintype "bidirectional"))
    )
    (net (code "92") (name "unconnected-(B7ALT-PadLC2)") (class "Default")
      (node (ref "B7ALT") (pin "LC2") (pinfunction "LC2_LC2") (pintype "bidirectional"))
    )
    (net (code "93") (name "unconnected-(B8-PadL3)") (class "Default")
      (node (ref "B8") (pin "L3") (pinfunction "L3_L3") (pintype "bidirectional"))
    )
    (net (code "94") (name "unconnected-(B8-PadL4)") (class "Default")
      (node (ref "B8") (pin "L4") (pinfunction "L4_L4") (pintype "bidirectional"))
    )
    (net (code "95") (name "unconnected-(B8-PadLC2)") (class "Default")
      (node (ref "B8") (pin "LC2") (pinfunction "LC2_LC2") (pintype "bidirectional"))
    )
    (net (code "96") (name "unconnected-(B8ALT-PadL3)") (class "Default")
      (node (ref "B8ALT") (pin "L3") (pinfunction "L3_L3") (pintype "bidirectional"))
    )
    (net (code "97") (name "unconnected-(B8ALT-PadL4)") (class "Default")
      (node (ref "B8ALT") (pin "L4") (pinfunction "L4_L4") (pintype "bidirectional"))
    )
    (net (code "98") (name "unconnected-(B8ALT-PadLC2)") (class "Default")
      (node (ref "B8ALT") (pin "LC2") (pinfunction "LC2_LC2") (pintype "bidirectional"))
    )
    (net (code "99") (name "unconnected-(B9-PadL3)") (class "Default")
      (node (ref "B9") (pin "L3") (pinfunction "L3_L3") (pintype "bidirectional"))
    )
    (net (code "100") (name "unconnected-(B9-PadL4)") (class "Default")
      (node (ref "B9") (pin "L4") (pinfunction "L4_L4") (pintype "bidirectional"))
    )
    (net (code "101") (name "unconnected-(B9-PadLC2)") (class "Default")
      (node (ref "B9") (pin "LC2") (pinfunction "LC2_LC2") (pintype "bidirectional"))
    )
    (net (code "102") (name "unconnected-(B9ALT-PadL3)") (class "Default")
      (node (ref "B9ALT") (pin "L3") (pinfunction "L3_L3") (pintype "bidirectional"))
    )
    (net (code "103") (name "unconnected-(B9ALT-PadL4)") (class "Default")
      (node (ref "B9ALT") (pin "L4") (pinfunction "L4_L4") (pintype "bidirectional"))
    )
    (net (code "104") (name "unconnected-(B9ALT-PadLC2)") (class "Default")
      (node (ref "B9ALT") (pin "LC2") (pinfunction "LC2_LC2") (pintype "bidirectional"))
    )
    (net (code "105") (name "unconnected-(B10-PadL3)") (class "Default")
      (node (ref "B10") (pin "L3") (pinfunction "L3_L3") (pintype "bidirectional"))
    )
    (net (code "106") (name "unconnected-(B10-PadL4)") (class "Default")
      (node (ref "B10") (pin "L4") (pinfunction "L4_L4") (pintype "bidirectional"))
    )
    (net (code "107") (name "unconnected-(B10-PadLC2)") (class "Default")
      (node (ref "B10") (pin "LC2") (pinfunction "LC2_LC2") (pintype "bidirectional"))
    )
    (net (code "108") (name "unconnected-(B10ALT-PadL3)") (class "Default")
      (node (ref "B10ALT") (pin "L3") (pinfunction "L3_L3") (pintype "bidirectional"))
    )
    (net (code "109") (name "unconnected-(B10ALT-PadL4)") (class "Default")
      (node (ref "B10ALT") (pin "L4") (pinfunction "L4_L4") (pintype "bidirectional"))
    )
    (net (code "110") (name "unconnected-(B10ALT-PadLC2)") (class "Default")
      (node (ref "B10ALT") (pin "LC2") (pinfunction "LC2_LC2") (pintype "bidirectional"))
    )
    (net (code "111") (name "unconnected-(B11-PadL3)") (class "Default")
      (node (ref "B11") (pin "L3") (pinfunction "L3_L3") (pintype "bidirectional"))
    )
    (net (code "112") (name "unconnected-(B11-PadL4)") (class "Default")
      (node (ref "B11") (pin "L4") (pinfunction "L4_L4") (pintype "bidirectional"))
    )
    (net (code "113") (name "unconnected-(B11-PadLC2)") (class "Default")
      (node (ref "B11") (pin "LC2") (pinfunction "LC2_LC2") (pintype "bidirectional"))
    )
    (net (code "114") (name "unconnected-(B11ALT-PadL3)") (class "Default")
      (node (ref "B11ALT") (pin "L3") (pinfunction "L3_L3") (pintype "bidirectional"))
    )
    (net (code "115") (name "unconnected-(B11ALT-PadL4)") (class "Default")
      (node (ref "B11ALT") (pin "L4") (pinfunction "L4_L4") (pintype "bidirectional"))
    )
    (net (code "116") (name "unconnected-(B11ALT-PadLC2)") (class "Default")
      (node (ref "B11ALT") (pin "LC2") (pinfunction "LC2_LC2") (pintype "bidirectional"))
    )
    (net (code "117") (name "unconnected-(B12-PadL3)") (class "Default")
      (node (ref "B12") (pin "L3") (pinfunction "L3_L3") (pintype "bidirectional"))
    )
    (net (code "118") (name "unconnected-(B12-PadL4)") (class "Default")
      (node (ref "B12") (pin "L4") (pinfunction "L4_L4") (pintype "bidirectional"))
    )
    (net (code "119") (name "unconnected-(B12-PadLC2)") (class "Default")
      (node (ref "B12") (pin "LC2") (pinfunction "LC2_LC2") (pintype "bidirectional"))
    )
    (net (code "120") (name "unconnected-(B12ALT-PadL3)") (class "Default")
      (node (ref "B12ALT") (pin "L3") (pinfunction "L3_L3") (pintype "bidirectional"))
    )
    (net (code "121") (name "unconnected-(B12ALT-PadL4)") (class "Default")
      (node (ref "B12ALT") (pin "L4") (pinfunction "L4_L4") (pintype "bidirectional"))
    )
    (net (code "122") (name "unconnected-(B12ALT-PadLC2)") (class "Default")
      (node (ref "B12ALT") (pin "LC2") (pinfunction "LC2_LC2") (pintype "bidirectional"))
    )
    (net (code "123") (name "unconnected-(B13-PadL3)") (class "Default")
      (node (ref "B13") (pin "L3") (pinfunction "L3_L3") (pintype "bidirectional"))
    )
    (net (code "124") (name "unconnected-(B13-PadL4)") (class "Default")
      (node (ref "B13") (pin "L4") (pinfunction "L4_L4") (pintype "bidirectional"))
    )
    (net (code "125") (name "unconnected-(B13-PadLC2)") (class "Default")
      (node (ref "B13") (pin "LC2") (pinfunction "LC2_LC2") (pintype "bidirectional"))
    )
    (net (code "126") (name "unconnected-(B14-PadL3)") (class "Default")
      (node (ref "B14") (pin "L3") (pinfunction "L3_L3") (pintype "bidirectional"))
    )
    (net (code "127") (name "unconnected-(B14-PadL4)") (class "Default")
      (node (ref "B14") (pin "L4") (pinfunction "L4_L4") (pintype "bidirectional"))
    )
    (net (code "128") (name "unconnected-(B14-PadLC2)") (class "Default")
      (node (ref "B14") (pin "LC2") (pinfunction "LC2_LC2") (pintype "bidirectional"))
    )
    (net (code "129") (name "unconnected-(B15-PadL3)") (class "Default")
      (node (ref "B15") (pin "L3") (pinfunction "L3_L3") (pintype "bidirectional"))
    )
    (net (code "130") (name "unconnected-(B15-PadL4)") (class "Default")
      (node (ref "B15") (pin "L4") (pinfunction "L4_L4") (pintype "bidirectional"))
    )
    (net (code "131") (name "unconnected-(B15-PadLC2)") (class "Default")
      (node (ref "B15") (pin "LC2") (pinfunction "LC2_LC2") (pintype "bidirectional"))
    )
    (net (code "132") (name "unconnected-(B16-PadL3)") (class "Default")
      (node (ref "B16") (pin "L3") (pinfunction "L3_L3") (pintype "bidirectional"))
    )
    (net (code "133") (name "unconnected-(B16-PadL4)") (class "Default")
      (node (ref "B16") (pin "L4") (pinfunction "L4_L4") (pintype "bidirectional"))
    )
    (net (code "134") (name "unconnected-(B16-PadLC2)") (class "Default")
      (node (ref "B16") (pin "LC2") (pinfunction "LC2_LC2") (pintype "bidirectional"))
    )
    (net (code "135") (name "unconnected-(IC1-INTA-Pad20)") (class "Default")
      (node (ref "IC1") (pin "20") (pinfunction "INTA_20") (pintype "output"))
    )
    (net (code "136") (name "unconnected-(IC1-INTB-Pad19)") (class "Default")
      (node (ref "IC1") (pin "19") (pinfunction "INTB_19") (pintype "output"))
    )
  )
)
